# IMU_breakout.net
KiCad netlist of a schematic drawn in Altium Designer
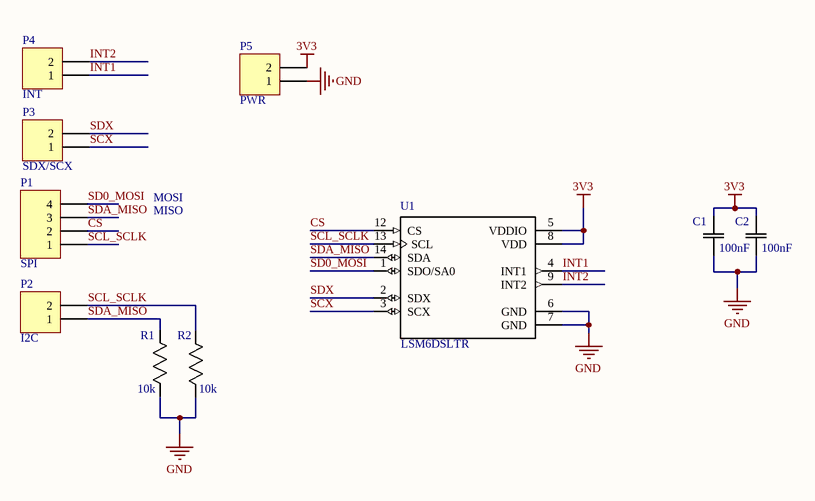
[diagram p0: IMU_breakout.SchDoc]

(export (version "E")
  (design (tool "Eeschema 10.0.6"))
  (components
    (comp (ref "C1")
      (value "100nF")
      (footprint "0805")
      (description "CAP CER 0.1UF 50V X7R 0805")
      (fields (field (name "MP") "CC0805KRX7R9BB104") (field (name "MF") "Yageo"))
      (libsource (lib "AltiumLibraries") (part "CAP 100nF 0805"))
    )
    (comp (ref "C2")
      (value "100nF")
      (footprint "0805")
      (description "CAP CER 0.1UF 50V X7R 0805")
      (fields (field (name "MP") "CC0805KRX7R9BB104") (field (name "MF") "Yageo"))
      (libsource (lib "AltiumLibraries") (part "CAP 100nF 0805"))
    )
    (comp (ref "P1")
      (value "SPI")
      (footprint "HDR1X4")
      (description "Header, 4-Pin")
      (fields (field (name "PUBLISHER") "Altium Limited"))
      (libsource (lib "Miscellaneous Connectors") (part "Header 4"))
    )
    (comp (ref "P2")
      (value "I2C")
      (footprint "HDR1X2")
      (description "Header, 2-Pin")
      (fields (field (name "PUBLISHER") "Altium Limited"))
      (libsource (lib "Miscellaneous Connectors") (part "Header 2"))
    )
    (comp (ref "P3")
      (value "SDX/SCX")
      (footprint "HDR1X2")
      (description "Header, 2-Pin")
      (fields (field (name "PUBLISHER") "Altium Limited"))
      (libsource (lib "Miscellaneous Connectors") (part "Header 2"))
    )
    (comp (ref "P4")
      (value "INT")
      (footprint "HDR1X2")
      (description "Header, 2-Pin")
      (fields (field (name "PUBLISHER") "Altium Limited"))
      (libsource (lib "Miscellaneous Connectors") (part "Header 2"))
    )
    (comp (ref "P5")
      (value "PWR")
      (footprint "HDR1X2")
      (description "Header, 2-Pin")
      (fields (field (name "PUBLISHER") "Altium Limited"))
      (libsource (lib "Miscellaneous Connectors") (part "Header 2"))
    )
    (comp (ref "R1")
      (value "10k")
      (footprint "0805")
      (description "RES SMD 10K OHM 1% 1/8W 0805")
      (fields (field (name "MP") "RC0805FR-0710KL") (field (name "MF") "Yageo"))
      (libsource (lib "AltiumLibraries") (part "RES 10k 0805"))
    )
    (comp (ref "R2")
      (value "10k")
      (footprint "0805")
      (description "RES SMD 10K OHM 1% 1/8W 0805")
      (fields (field (name "MP") "RC0805FR-0710KL") (field (name "MF") "Yageo"))
      (libsource (lib "AltiumLibraries") (part "RES 10k 0805"))
    )
    (comp (ref "U1")
      (value "LSM6DSLTR")
      (footprint "LGA-14")
      (description "Accelerometer, Gyroscope, Temperature, 6 Axis Sensor IÂ²C, SPI Output")
      (fields (field (name "MF") "STMicroelectronics"))
      (libsource (lib "AltiumLibraries") (part "LSM6DSLTR"))
    )
  )
  (nets
    (net (code "1") (name "/CS") (class "Default")
      (node (ref "P1") (pin "2") (pinfunction "2_2") (pintype "passive"))
      (node (ref "U1") (pin "12") (pinfunction "CS_12") (pintype "input"))
    )
    (net (code "2") (name "/INT1") (class "Default")
      (node (ref "P4") (pin "1") (pinfunction "1_1") (pintype "passive"))
      (node (ref "U1") (pin "4") (pinfunction "INT1_4") (pintype "output"))
    )
    (net (code "3") (name "/INT2") (class "Default")
      (node (ref "P4") (pin "2") (pinfunction "2_2") (pintype "passive"))
      (node (ref "U1") (pin "9") (pinfunction "INT2_9") (pintype "output"))
    )
    (net (code "4") (name "/SCL_SCLK") (class "Default")
      (node (ref "P1") (pin "1") (pinfunction "1_1") (pintype "passive"))
      (node (ref "P2") (pin "2") (pinfunction "2_2") (pintype "passive"))
      (node (ref "R2") (pin "1") (pinfunction "R1_1") (pintype "passive"))
      (node (ref "U1") (pin "13") (pinfunction "SCL_13") (pintype "input"))
    )
    (net (code "5") (name "/SCX") (class "Default")
      (node (ref "P3") (pin "1") (pinfunction "1_1") (pintype "passive"))
      (node (ref "U1") (pin "3") (pinfunction "SCX_3") (pintype "bidirectional"))
    )
    (net (code "6") (name "/SD0_MOSI") (class "Default")
      (node (ref "P1") (pin "4") (pinfunction "4_4") (pintype "passive"))
      (node (ref "U1") (pin "1") (pinfunction "SDO/SA0_1") (pintype "bidirectional"))
    )
    (net (code "7") (name "/SDA_MISO") (class "Default")
      (node (ref "P1") (pin "3") (pinfunction "3_3") (pintype "passive"))
      (node (ref "P2") (pin "1") (pinfunction "1_1") (pintype "passive"))
      (node (ref "R1") (pin "1") (pinfunction "R1_1") (pintype "passive"))
      (node (ref "U1") (pin "14") (pinfunction "SDA_14") (pintype "bidirectional"))
    )
    (net (code "8") (name "/SDX") (class "Default")
      (node (ref "P3") (pin "2") (pinfunction "2_2") (pintype "passive"))
      (node (ref "U1") (pin "2") (pinfunction "SDX_2") (pintype "bidirectional"))
    )
    (net (code "9") (name "3V3") (class "Default")
      (node (ref "C1") (pin "2") (pinfunction "C2_2") (pintype "passive"))
      (node (ref "C2") (pin "2") (pinfunction "C2_2") (pintype "passive"))
      (node (ref "P5") (pin "2") (pinfunction "2_2") (pintype "passive"))
      (node (ref "U1") (pin "5") (pinfunction "VDDIO_5") (pintype "power_in"))
      (node (ref "U1") (pin "8") (pinfunction "VDD_8") (pintype "power_in"))
    )
    (net (code "10") (name "GND") (class "Default")
      (node (ref "C1") (pin "1") (pinfunction "C1_1") (pintype "passive"))
      (node (ref "C2") (pin "1") (pinfunction "C1_1") (pintype "passive"))
      (node (ref "P5") (pin "1") (pinfunction "1_1") (pintype "passive"))
      (node (ref "R1") (pin "2") (pinfunction "R2_2") (pintype "passive"))
      (node (ref "R2") (pin "2") (pinfunction "R2_2") (pintype "passive"))
      (node (ref "U1") (pin "6") (pinfunction "GND_6") (pintype "power_in"))
      (node (ref "U1") (pin "7") (pinfunction "GND_7") (pintype "power_in"))
    )
  )
)
